# Motor_Control.net
KiCad netlist of a schematic drawn in Altium Designer
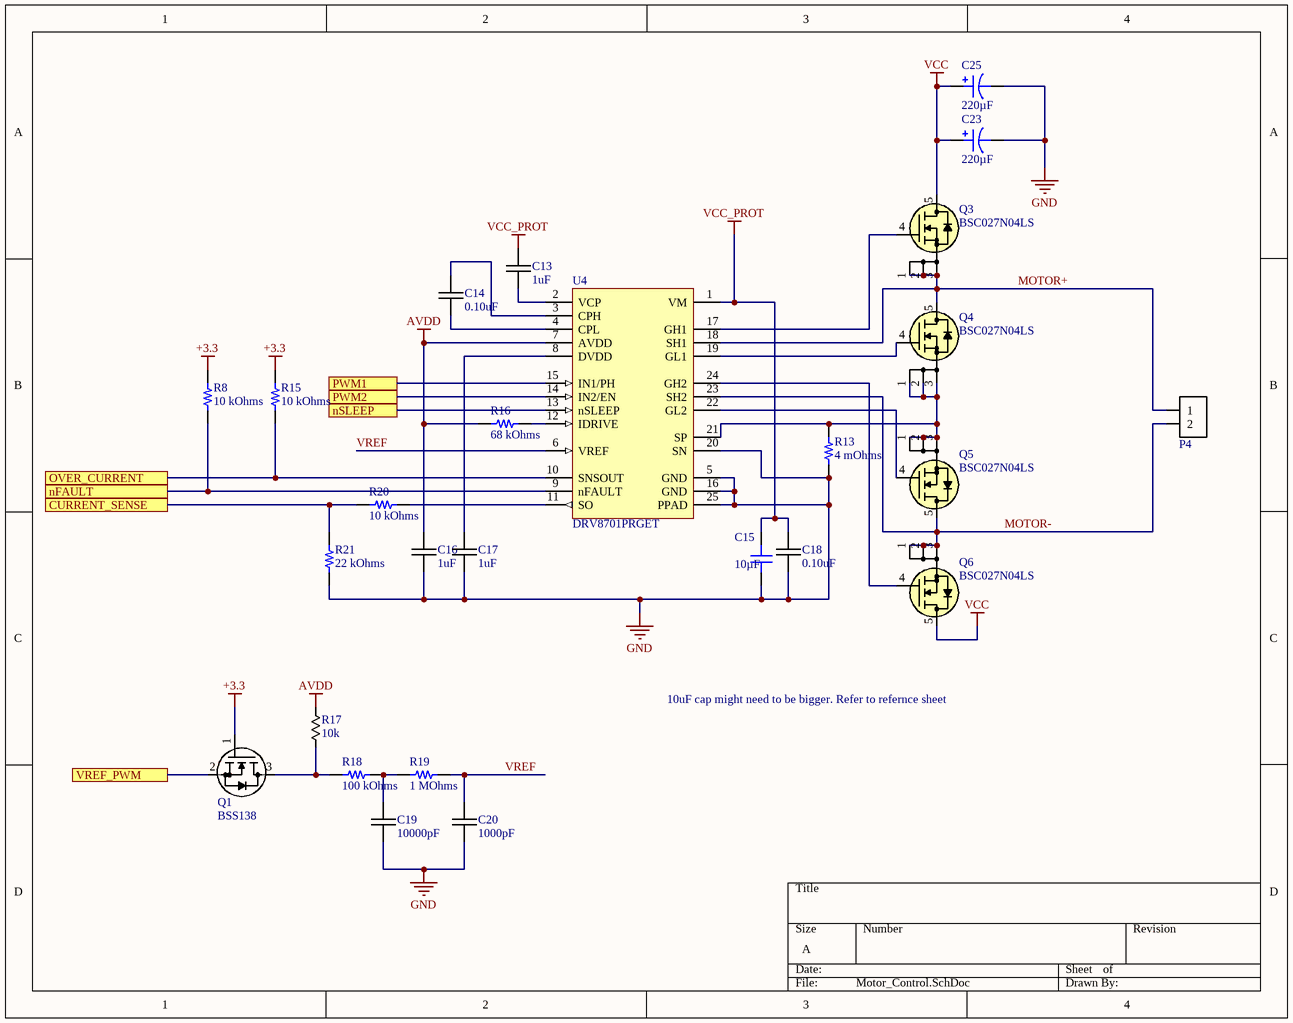
[diagram p0: Motor_Control.SchDoc]

(export (version "E")
  (design (tool "Eeschema 10.0.6"))
  (components
    (comp (ref "C13")
      (value "1uF")
      (footprint "chip_0805")
      (description "CAP, 1uF, 10%, 50V, X7R, 0805")
      (fields (field (name "PART NUMBER") "CAP-00109") (field (name "TOLERANCE") "10%"))
      (libsource (lib "Capacitors$") (part "CAP-00109"))
    )
    (comp (ref "C14")
      (value "0.10uF")
      (footprint "chip_0805")
      (description "CAP, 0.10uF, 10%, 50V, X7R, 0805")
      (fields (field (name "PART NUMBER") "CAP-00070") (field (name "TOLERANCE") "10%"))
      (libsource (lib "Capacitors$") (part "CAP-00070"))
    )
    (comp (ref "C15")
      (value "10µF")
      (footprint "CAP 1206_3216 - 1.8MM")
      (description "CAP CER 10UF 50V X7R 1206")
      (fields
        (field (name "PART NUMBER") "CL31B106KBHNNNE")
        (field (name "MANUFACTURER") "Samsung Electro-Mechanics")
      )
      (libsource (lib "Celestial Altium Library - altium_library") (part "Capacitor"))
    )
    (comp (ref "C16")
      (value "1uF")
      (footprint "chip_0805")
      (description "CAP, 1uF, 10%, 50V, X7R, 0805")
      (fields (field (name "PART NUMBER") "CAP-00109") (field (name "TOLERANCE") "10%"))
      (libsource (lib "Capacitors$") (part "CAP-00109"))
    )
    (comp (ref "C17")
      (value "1uF")
      (footprint "chip_0805")
      (description "CAP, 1uF, 10%, 50V, X7R, 0805")
      (fields (field (name "PART NUMBER") "CAP-00109") (field (name "TOLERANCE") "10%"))
      (libsource (lib "Capacitors$") (part "CAP-00109"))
    )
    (comp (ref "C18")
      (value "0.10uF")
      (footprint "chip_0805")
      (description "CAP, 0.10uF, 10%, 50V, X7R, 0805")
      (fields (field (name "PART NUMBER") "CAP-00070") (field (name "TOLERANCE") "10%"))
      (libsource (lib "Capacitors$") (part "CAP-00070"))
    )
    (comp (ref "C19")
      (value "10000pF")
      (footprint "chip_0805")
      (description "CAP, 10000pF, 10%, 50V, X7R, 0805")
      (fields (field (name "PART NUMBER") "CAP-00040") (field (name "TOLERANCE") "10%"))
      (libsource (lib "Capacitors$") (part "CAP-00040"))
    )
    (comp (ref "C20")
      (value "1000pF")
      (footprint "chip_0603")
      (description "CAP, 1000pF, ±1%, 50V, C0G, 0603")
      (fields (field (name "PART NUMBER") "CAP-00457") (field (name "TOLERANCE") "±1%"))
      (libsource (lib "Capacitors$") (part "CAP-00457"))
    )
    (comp (ref "C23")
      (value "220µF")
      (footprint "CAP TH ALUM ELEC D10.00mm S5.00mm H13.50mm")
      (description "CAP ALUM 220UF 50V 20% RADIAL")
      (fields
        (field (name "PART NUMBER") "ECA-1HHG221B")
        (field (name "MANUFACTURER") "Panasonic Electronic Components")
      )
      (libsource (lib "Celestial Altium Library - altium_library") (part "Polarised Capacitor"))
    )
    (comp (ref "C25")
      (value "220µF")
      (footprint "CAP TH ALUM ELEC D10.00mm S5.00mm H13.50mm")
      (description "CAP ALUM 220UF 50V 20% RADIAL")
      (fields
        (field (name "PART NUMBER") "ECA-1HHG221B")
        (field (name "MANUFACTURER") "Panasonic Electronic Components")
      )
      (libsource (lib "Celestial Altium Library - altium_library") (part "Polarised Capacitor"))
    )
    (comp (ref "P4")
      (value "conn-2x1_0")
      (footprint "BARR_0.5IN_2x1_0")
      (description "Barrier Blk, 2 Pos, 50 A")
      (fields (field (name "PART NUMBER") "CONN-00001") (field (name "MANUFACTURER") "Molex"))
      (libsource (lib "Connectors") (part "conn-2x1_0"))
    )
    (comp (ref "Q1")
      (value "n-mosfet_1")
      (footprint "sot-23-3")
      (description "XSTR NMOS, 220mA, 50V, Vgs 1.3V, SOT-23-3")
      (fields
        (field (name "MANUFACTURER PN") "BSS138")
        (field (name "PART NUMBER") "XSTR-00017")
        (field (name "MANUFACTURER") "ON Semi")
      )
      (libsource (lib "Transistors") (part "n-mosfet_1"))
    )
    (comp (ref "Q3")
      (value "BSC027N04LS")
      (footprint "TDFN-8-5x6")
      (description "XSTR, MOSFET N-Channel, 40V 100A TDFN-8")
      (fields (field (name "PART NUMBER") "XSTR-00049") (field (name "MANUFACTURER") "Infineon"))
      (libsource (lib "cwrubotix_library") (part "n-mosfet-SSSGD"))
    )
    (comp (ref "Q4")
      (value "BSC027N04LS")
      (footprint "TDFN-8-5x6")
      (description "XSTR, MOSFET N-Channel, 40V 100A TDFN-8")
      (fields (field (name "PART NUMBER") "XSTR-00049") (field (name "MANUFACTURER") "Infineon"))
      (libsource (lib "cwrubotix_library") (part "n-mosfet-SSSGD"))
    )
    (comp (ref "Q5")
      (value "BSC027N04LS")
      (footprint "TDFN-8-5x6")
      (description "XSTR, MOSFET N-Channel, 40V 100A TDFN-8")
      (fields (field (name "PART NUMBER") "XSTR-00049") (field (name "MANUFACTURER") "Infineon"))
      (libsource (lib "cwrubotix_library") (part "n-mosfet-SSSGD"))
    )
    (comp (ref "Q6")
      (value "BSC027N04LS")
      (footprint "TDFN-8-5x6")
      (description "XSTR, MOSFET N-Channel, 40V 100A TDFN-8")
      (fields (field (name "PART NUMBER") "XSTR-00049") (field (name "MANUFACTURER") "Infineon"))
      (libsource (lib "cwrubotix_library") (part "n-mosfet-SSSGD"))
    )
    (comp (ref "R8")
      (value "10 kOhms")
      (footprint "RES 0805_2012")
      (description "RES 10K OHM 5% 1/4W 0805")
      (fields
        (field (name "PART NUMBER") "SG73S2ATTD103J")
        (field (name "MANUFACTURER") "KOA Speer Electronics, Inc.")
      )
      (libsource (lib "Celestial Altium Library - altium_library") (part "Resistor"))
    )
    (comp (ref "R13")
      (value "4 mOhms")
      (footprint "RES 2512_6432")
      (description "RES 0.004 OHM 1% 3W 2512")
      (fields (field (name "PART NUMBER") "PA2512FKE7T0R004E") (field (name "MANUFACTURER") "Yageo"))
      (libsource (lib "Celestial Altium Library - altium_library") (part "Resistor"))
    )
    (comp (ref "R15")
      (value "10 kOhms")
      (footprint "RES 0805_2012")
      (description "RES 10K OHM 5% 1/4W 0805")
      (fields
        (field (name "PART NUMBER") "SG73S2ATTD103J")
        (field (name "MANUFACTURER") "KOA Speer Electronics, Inc.")
      )
      (libsource (lib "Celestial Altium Library - altium_library") (part "Resistor"))
    )
    (comp (ref "R16")
      (value "68 kOhms")
      (footprint "RES 0805_2012")
      (description "RES 68K OHM 0.05% 1/8W 0805")
      (fields
        (field (name "PART NUMBER") "ERA-6ARW683V")
        (field (name "MANUFACTURER") "Panasonic Electronic Components")
      )
      (libsource (lib "Celestial Altium Library - altium_library") (part "Resistor"))
    )
    (comp (ref "R17")
      (value "10k")
      (footprint "chip_0805")
      (description "RES SMD 10K OHM 1% 1/8W 0805")
      (fields (field (name "PART NUMBER") "RES-00307") (field (name "TOLERANCE") "1%"))
      (libsource (lib "Resistors$") (part "RES-00307"))
    )
    (comp (ref "R18")
      (value "100 kOhms")
      (footprint "RES 0603_1608")
      (description "RES SMD 100K OHM 1% 1/4W 0603")
      (fields (field (name "PART NUMBER") "CRCW0603100KFKEAHP") (field (name "MANUFACTURER") "Vishay Dale"))
      (libsource (lib "Celestial Altium Library - altium_library") (part "Resistor"))
    )
    (comp (ref "R19")
      (value "1 MOhms")
      (footprint "RES 0603_1608")
      (description "RES SMD 1M OHM 1% 1/4W 0603")
      (fields (field (name "PART NUMBER") "RCS06031M00FKEA") (field (name "MANUFACTURER") "Vishay Dale"))
      (libsource (lib "Celestial Altium Library - altium_library") (part "Resistor"))
    )
    (comp (ref "R20")
      (value "10 kOhms")
      (footprint "RES 0805_2012")
      (description "RES 10K OHM 5% 1/4W 0805")
      (fields
        (field (name "PART NUMBER") "SG73S2ATTD103J")
        (field (name "MANUFACTURER") "KOA Speer Electronics, Inc.")
      )
      (libsource (lib "Celestial Altium Library - altium_library") (part "Resistor"))
    )
    (comp (ref "R21")
      (value "22 kOhms")
      (footprint "RES 0805_2012")
      (description "RES SMD 22K OHM 1% 1/8W 0805")
      (fields (field (name "PART NUMBER") "RC0805FR-0722KL") (field (name "MANUFACTURER") "Yageo"))
      (libsource (lib "Celestial Altium Library - altium_library") (part "Resistor"))
    )
    (comp (ref "U4")
      (value "DRV8701PRGET")
      (footprint "VQFN-24-EP")
      (description "Dual Half-Bridge Driver, PWM, 5.9-45V, DRV8701P")
      (fields (field (name "PART NUMBER") "PWREG-00045") (field (name "MANUFACTURER") "TI"))
      (libsource (lib "Power Reg") (part "DRV8701"))
    )
  )
  (nets
    (net (code "1") (name "+3.3") (class "Default")
      (node (ref "Q1") (pin "1") (pinfunction "G_1") (pintype "passive"))
      (node (ref "R15") (pin "2") (pinfunction "2_2") (pintype "passive"))
      (node (ref "R8") (pin "2") (pinfunction "2_2") (pintype "passive"))
    )
    (net (code "2") (name "/CURRENT_SENSE") (class "Default")
      (node (ref "R20") (pin "2") (pinfunction "2_2") (pintype "passive"))
      (node (ref "R21") (pin "2") (pinfunction "2_2") (pintype "passive"))
    )
    (net (code "3") (name "/MOTOR+") (class "Default")
      (node (ref "P4") (pin "1") (pinfunction "1_1") (pintype "passive"))
      (node (ref "Q3") (pin "1") (pinfunction "S_1") (pintype "passive"))
      (node (ref "Q3") (pin "2") (pinfunction "S_2") (pintype "passive"))
      (node (ref "Q3") (pin "3") (pinfunction "S_3") (pintype "passive"))
      (node (ref "Q4") (pin "5") (pinfunction "D_5") (pintype "passive"))
      (node (ref "U4") (pin "18") (pinfunction "SH1_18") (pintype "passive"))
    )
    (net (code "4") (name "/MOTOR-") (class "Default")
      (node (ref "P4") (pin "2") (pinfunction "2_2") (pintype "passive"))
      (node (ref "Q5") (pin "5") (pinfunction "D_5") (pintype "passive"))
      (node (ref "Q6") (pin "1") (pinfunction "S_1") (pintype "passive"))
      (node (ref "Q6") (pin "2") (pinfunction "S_2") (pintype "passive"))
      (node (ref "Q6") (pin "3") (pinfunction "S_3") (pintype "passive"))
      (node (ref "U4") (pin "23") (pinfunction "SH2_23") (pintype "passive"))
    )
    (net (code "5") (name "/OVER_CURRENT") (class "Default")
      (node (ref "R15") (pin "1") (pinfunction "1_1") (pintype "passive"))
      (node (ref "U4") (pin "10") (pinfunction "SNSOUT_10") (pintype "open_collector"))
    )
    (net (code "6") (name "/PWM1") (class "Default")
      (node (ref "U4") (pin "15") (pinfunction "IN1/PH_15") (pintype "input"))
    )
    (net (code "7") (name "/PWM2") (class "Default")
      (node (ref "U4") (pin "14") (pinfunction "IN2/EN_14") (pintype "input"))
    )
    (net (code "8") (name "/VREF") (class "Default")
      (node (ref "C20") (pin "1") (pinfunction "1_1") (pintype "passive"))
      (node (ref "R19") (pin "2") (pinfunction "2_2") (pintype "passive"))
      (node (ref "U4") (pin "6") (pinfunction "VREF_6") (pintype "input"))
    )
    (net (code "9") (name "/VREF_PWM") (class "Default")
      (node (ref "Q1") (pin "2") (pinfunction "S_2") (pintype "passive"))
    )
    (net (code "10") (name "/nFAULT") (class "Default")
      (node (ref "R8") (pin "1") (pinfunction "1_1") (pintype "passive"))
      (node (ref "U4") (pin "9") (pinfunction "nFAULT_9") (pintype "open_collector"))
    )
    (net (code "11") (name "/nSLEEP") (class "Default")
      (node (ref "U4") (pin "13") (pinfunction "nSLEEP_13") (pintype "input"))
    )
    (net (code "12") (name "AVDD") (class "Default")
      (node (ref "C16") (pin "1") (pinfunction "1_1") (pintype "passive"))
      (node (ref "R16") (pin "1") (pinfunction "1_1") (pintype "passive"))
      (node (ref "R17") (pin "1") (pinfunction "1_1") (pintype "passive"))
      (node (ref "U4") (pin "7") (pinfunction "AVDD_7") (pintype "power_in"))
    )
    (net (code "13") (name "GND") (class "Default")
      (node (ref "C15") (pin "1") (pinfunction "1_1") (pintype "passive"))
      (node (ref "C16") (pin "2") (pinfunction "2_2") (pintype "passive"))
      (node (ref "C17") (pin "2") (pinfunction "2_2") (pintype "passive"))
      (node (ref "C18") (pin "2") (pinfunction "2_2") (pintype "passive"))
      (node (ref "C19") (pin "2") (pinfunction "2_2") (pintype "passive"))
      (node (ref "C20") (pin "2") (pinfunction "2_2") (pintype "passive"))
      (node (ref "C23") (pin "2") (pinfunction "2_2") (pintype "passive"))
      (node (ref "C25") (pin "2") (pinfunction "2_2") (pintype "passive"))
      (node (ref "R13") (pin "1") (pinfunction "1_1") (pintype "passive"))
      (node (ref "R21") (pin "1") (pinfunction "1_1") (pintype "passive"))
      (node (ref "U4") (pin "16") (pinfunction "GND_16") (pintype "power_in"))
      (node (ref "U4") (pin "20") (pinfunction "SN_20") (pintype "passive"))
      (node (ref "U4") (pin "25") (pinfunction "PPAD_25") (pintype "power_in"))
      (node (ref "U4") (pin "5") (pinfunction "GND_5") (pintype "power_in"))
    )
    (net (code "14") (name "Net-(C19-Pad1)") (class "Default")
      (node (ref "C19") (pin "1") (pinfunction "1_1") (pintype "passive"))
      (node (ref "R18") (pin "2") (pinfunction "2_2") (pintype "passive"))
      (node (ref "R19") (pin "1") (pinfunction "1_1") (pintype "passive"))
    )
    (net (code "15") (name "Net-(Q1-D)") (class "Default")
      (node (ref "Q1") (pin "3") (pinfunction "D_3") (pintype "passive"))
      (node (ref "R17") (pin "2") (pinfunction "2_2") (pintype "passive"))
      (node (ref "R18") (pin "1") (pinfunction "1_1") (pintype "passive"))
    )
    (net (code "16") (name "Net-(Q3-G)") (class "Default")
      (node (ref "Q3") (pin "4") (pinfunction "G_4") (pintype "passive"))
      (node (ref "U4") (pin "17") (pinfunction "GH1_17") (pintype "passive"))
    )
    (net (code "17") (name "Net-(Q4-G)") (class "Default")
      (node (ref "Q4") (pin "4") (pinfunction "G_4") (pintype "passive"))
      (node (ref "U4") (pin "19") (pinfunction "GL1_19") (pintype "passive"))
    )
    (net (code "18") (name "Net-(Q5-G)") (class "Default")
      (node (ref "Q5") (pin "4") (pinfunction "G_4") (pintype "passive"))
      (node (ref "U4") (pin "22") (pinfunction "GL2_22") (pintype "passive"))
    )
    (net (code "19") (name "Net-(Q6-G)") (class "Default")
      (node (ref "Q6") (pin "4") (pinfunction "G_4") (pintype "passive"))
      (node (ref "U4") (pin "24") (pinfunction "GH2_24") (pintype "passive"))
    )
    (net (code "20") (name "Net-(U4-CPH)") (class "Default")
      (node (ref "C14") (pin "1") (pinfunction "1_1") (pintype "passive"))
      (node (ref "U4") (pin "3") (pinfunction "CPH_3") (pintype "passive"))
    )
    (net (code "21") (name "Net-(U4-CPL)") (class "Default")
      (node (ref "C14") (pin "2") (pinfunction "2_2") (pintype "passive"))
      (node (ref "U4") (pin "4") (pinfunction "CPL_4") (pintype "passive"))
    )
    (net (code "22") (name "Net-(U4-DVDD)") (class "Default")
      (node (ref "C17") (pin "1") (pinfunction "1_1") (pintype "passive"))
      (node (ref "U4") (pin "8") (pinfunction "DVDD_8") (pintype "power_in"))
    )
    (net (code "23") (name "Net-(U4-IDRIVE)") (class "Default")
      (node (ref "R16") (pin "2") (pinfunction "2_2") (pintype "passive"))
      (node (ref "U4") (pin "12") (pinfunction "IDRIVE_12") (pintype "input"))
    )
    (net (code "24") (name "Net-(U4-SO)") (class "Default")
      (node (ref "R20") (pin "1") (pinfunction "1_1") (pintype "passive"))
      (node (ref "U4") (pin "11") (pinfunction "SO_11") (pintype "output"))
    )
    (net (code "25") (name "Net-(U4-SP)") (class "Default")
      (node (ref "Q4") (pin "1") (pinfunction "S_1") (pintype "passive"))
      (node (ref "Q4") (pin "2") (pinfunction "S_2") (pintype "passive"))
      (node (ref "Q4") (pin "3") (pinfunction "S_3") (pintype "passive"))
      (node (ref "Q5") (pin "1") (pinfunction "S_1") (pintype "passive"))
      (node (ref "Q5") (pin "2") (pinfunction "S_2") (pintype "passive"))
      (node (ref "Q5") (pin "3") (pinfunction "S_3") (pintype "passive"))
      (node (ref "R13") (pin "2") (pinfunction "2_2") (pintype "passive"))
      (node (ref "U4") (pin "21") (pinfunction "SP_21") (pintype "passive"))
    )
    (net (code "26") (name "Net-(U4-VCP)") (class "Default")
      (node (ref "C13") (pin "2") (pinfunction "2_2") (pintype "passive"))
      (node (ref "U4") (pin "2") (pinfunction "VCP_2") (pintype "passive"))
    )
    (net (code "27") (name "VCC") (class "Default")
      (node (ref "C23") (pin "1") (pinfunction "1_1") (pintype "passive"))
      (node (ref "C25") (pin "1") (pinfunction "1_1") (pintype "passive"))
      (node (ref "Q3") (pin "5") (pinfunction "D_5") (pintype "passive"))
      (node (ref "Q6") (pin "5") (pinfunction "D_5") (pintype "passive"))
    )
    (net (code "28") (name "VCC_PROT") (class "Default")
      (node (ref "C13") (pin "1") (pinfunction "1_1") (pintype "passive"))
      (node (ref "C15") (pin "2") (pinfunction "2_2") (pintype "passive"))
      (node (ref "C18") (pin "1") (pinfunction "1_1") (pintype "passive"))
      (node (ref "U4") (pin "1") (pinfunction "VM_1") (pintype "power_in"))
    )
  )
)
